# quadcopter.net
KiCad netlist of a schematic drawn in EAGLE
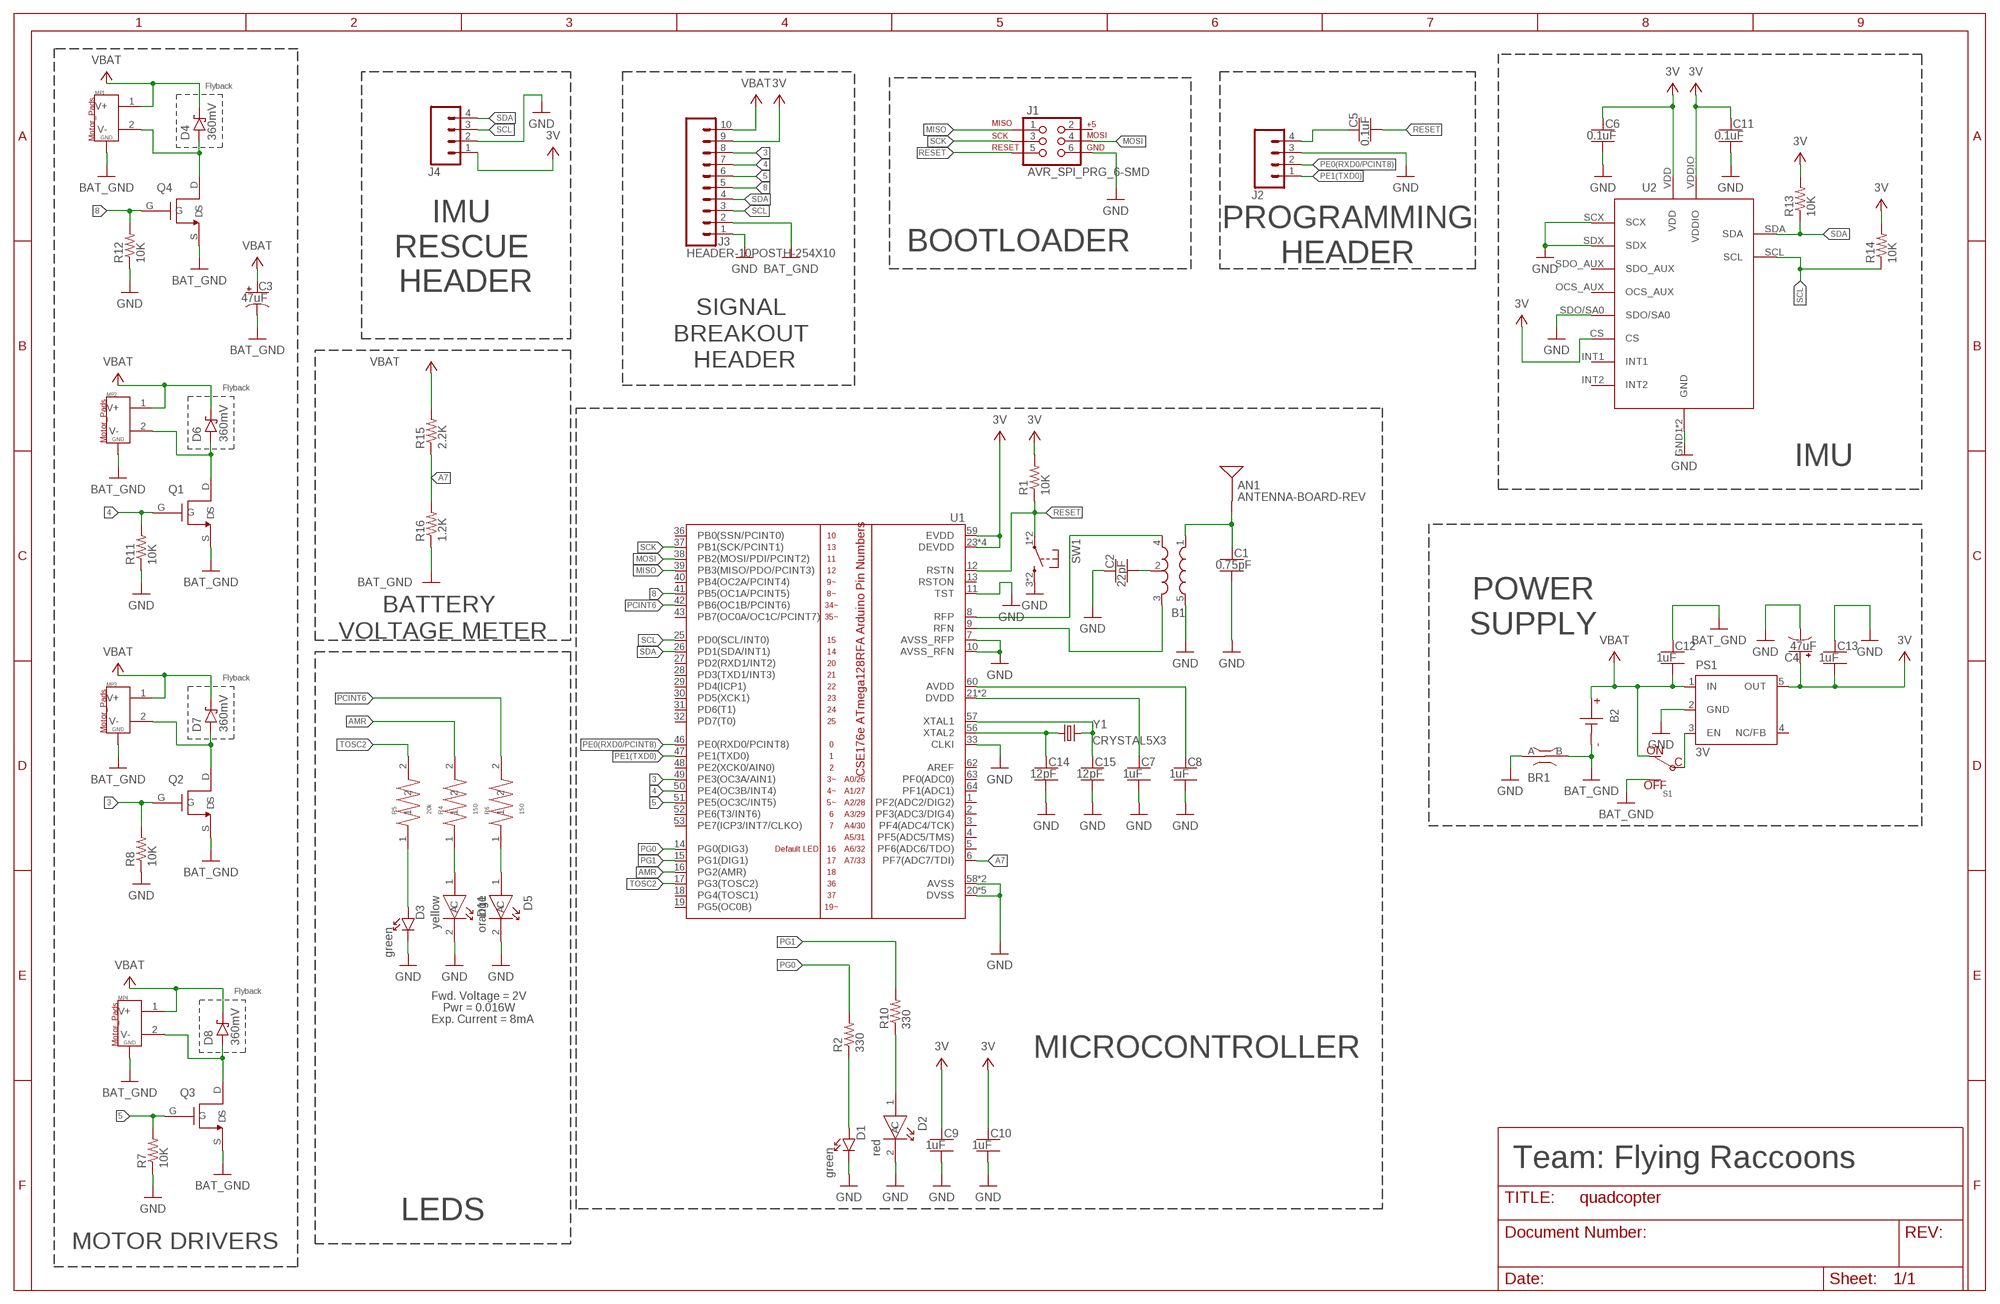
[diagram p0: schematic, sheet 1]

(export (version "E")
  (design (tool "Eeschema 10.0.6"))
  (components
    (comp (ref "AN1")
      (value "ANTENNA-BOARD-REV")
      (footprint "eagle-import:ANT_PCB_2.4GHZ_NRF8001_1.6MM_1OZ_REV")
      (fields (field (name "MFR") "NA") (field (name "CREATOR") "Swanson"))
      (libsource (lib "eagle-import") (part "ANTENNA-BOARD-REV"))
    )
    (comp (ref "B1")
      (value "BALUN0805")
      (footprint "eagle-import:BALUN")
      (fields
        (field (name "MFR") "Wurth Electronics Inc.")
        (field (name "MPN") "748421245")
        (field (name "CREATOR") "Swanson")
        (field (name "REVIEWER") "Swanson")
      )
      (libsource (lib "eagle-import") (part "BALUN0805"))
    )
    (comp (ref "B2")
      (value "BATTERY-SCREW-TERMINAL")
      (footprint "eagle-import:SCREW-TERMINAL-1X2-2.54MM")
      (fields (field (name "CREATOR") "Swanson"))
      (libsource (lib "eagle-import") (part "BATTERY-SCREW-TERMINAL"))
    )
    (comp (ref "BR1")
      (value "NET_BRIDGE-NET-BRIDGE")
      (footprint "eagle-import:BRIDGE")
      (fields (field (name "CREATOR") "Anish Kulkarni"))
      (libsource (lib "eagle-import") (part "NET_BRIDGE-NET-BRIDGE"))
    )
    (comp (ref "C1")
      (value "0.75pF")
      (footprint "eagle-import:CAPC2012X140_HS")
      (fields
        (field (name "MFR") "Murata Electronics")
        (field (name "MPN") "GQM2195C2AR75CB01D")
        (field (name "CREATOR") "Swanson")
        (field (name "REVIEWER") "Swanson")
      )
      (libsource (lib "eagle-import") (part "CAPACITOR-NP_SMD-2012-0805_CERAMIC-0.75PF"))
    )
    (comp (ref "C2")
      (value "22pF")
      (footprint "eagle-import:CAPC2012X140_HS")
      (fields
        (field (name "MFR") "Murata Electronics")
        (field (name "MPN") "GRM21A5C2E220JW01D")
        (field (name "CREATOR") "Swanson")
        (field (name "REVIEWER") "Swanson")
      )
      (libsource (lib "eagle-import") (part "CAPACITOR-NP_SMD-2012-0805_CERAMIC-22PF"))
    )
    (comp (ref "C3")
      (value "47uF")
      (footprint "eagle-import:CAPMP3216X180")
      (fields
        (field (name "MFR") "AVX Corporation")
        (field (name "MPN") "TAJA476K006SNJV")
        (field (name "CREATOR") "Swanson")
      )
      (libsource (lib "eagle-import") (part "CAPACITOR-POL_47UF-SMD-1206-TAJA"))
    )
    (comp (ref "C4")
      (value "47uF")
      (footprint "eagle-import:CAPMP3216X180")
      (fields
        (field (name "MFR") "AVX Corporation")
        (field (name "MPN") "TAJA476K006SNJV")
        (field (name "CREATOR") "Swanson")
      )
      (libsource (lib "eagle-import") (part "CAPACITOR-POL_47UF-SMD-1206-TAJA"))
    )
    (comp (ref "C5")
      (value "0.1uF")
      (footprint "eagle-import:CAPC2012X140_HS")
      (fields
        (field (name "MFR") "TDK Corporation")
        (field (name "MPN") "C2012X7R2A104K125AA")
        (field (name "CREATOR") "Swanson")
        (field (name "REVIEWER") "Swanson")
      )
      (libsource (lib "eagle-import") (part "CAPACITOR-NP_SMD-2012-0805_CERAMIC-0.1UF"))
    )
    (comp (ref "C6")
      (value "0.1uF")
      (footprint "eagle-import:CAPC2012X140_HS")
      (fields
        (field (name "MFR") "TDK Corporation")
        (field (name "MPN") "C2012X7R2A104K125AA")
        (field (name "CREATOR") "Swanson")
        (field (name "REVIEWER") "Swanson")
      )
      (libsource (lib "eagle-import") (part "CAPACITOR-NP_SMD-2012-0805_CERAMIC-0.1UF"))
    )
    (comp (ref "C7")
      (value "1uF")
      (footprint "eagle-import:CAPC2012X140_HS")
      (fields
        (field (name "MFR") "Taiyo Yuden")
        (field (name "MPN") "TMK212B7105KG-T")
        (field (name "CREATOR") "Swanson")
        (field (name "REVIEWER") "Swanson")
      )
      (libsource (lib "eagle-import") (part "CAPACITOR-NP_SMD-2012-0805_CERAMIC-1UF"))
    )
    (comp (ref "C8")
      (value "1uF")
      (footprint "eagle-import:CAPC2012X140_HS")
      (fields
        (field (name "MFR") "Taiyo Yuden")
        (field (name "MPN") "TMK212B7105KG-T")
        (field (name "CREATOR") "Swanson")
        (field (name "REVIEWER") "Swanson")
      )
      (libsource (lib "eagle-import") (part "CAPACITOR-NP_SMD-2012-0805_CERAMIC-1UF"))
    )
    (comp (ref "C9")
      (value "1uF")
      (footprint "eagle-import:CAPC2012X140_HS")
      (fields
        (field (name "MFR") "Taiyo Yuden")
        (field (name "MPN") "TMK212B7105KG-T")
        (field (name "CREATOR") "Swanson")
        (field (name "REVIEWER") "Swanson")
      )
      (libsource (lib "eagle-import") (part "CAPACITOR-NP_SMD-2012-0805_CERAMIC-1UF"))
    )
    (comp (ref "C10")
      (value "1uF")
      (footprint "eagle-import:CAPC2012X140_HS")
      (fields
        (field (name "MFR") "Taiyo Yuden")
        (field (name "MPN") "TMK212B7105KG-T")
        (field (name "CREATOR") "Swanson")
        (field (name "REVIEWER") "Swanson")
      )
      (libsource (lib "eagle-import") (part "CAPACITOR-NP_SMD-2012-0805_CERAMIC-1UF"))
    )
    (comp (ref "C11")
      (value "0.1uF")
      (footprint "eagle-import:CAPC2012X140_HS")
      (fields
        (field (name "MFR") "TDK Corporation")
        (field (name "MPN") "C2012X7R2A104K125AA")
        (field (name "CREATOR") "Swanson")
        (field (name "REVIEWER") "Swanson")
      )
      (libsource (lib "eagle-import") (part "CAPACITOR-NP_SMD-2012-0805_CERAMIC-0.1UF"))
    )
    (comp (ref "C12")
      (value "1uF")
      (footprint "eagle-import:CAPC2012X140_HS")
      (fields
        (field (name "MFR") "Taiyo Yuden")
        (field (name "MPN") "TMK212B7105KG-T")
        (field (name "CREATOR") "Swanson")
        (field (name "REVIEWER") "Swanson")
      )
      (libsource (lib "eagle-import") (part "CAPACITOR-NP_SMD-2012-0805_CERAMIC-1UF"))
    )
    (comp (ref "C13")
      (value "1uF")
      (footprint "eagle-import:CAPC2012X140_HS")
      (fields
        (field (name "MFR") "Taiyo Yuden")
        (field (name "MPN") "TMK212B7105KG-T")
        (field (name "CREATOR") "Swanson")
        (field (name "REVIEWER") "Swanson")
      )
      (libsource (lib "eagle-import") (part "CAPACITOR-NP_SMD-2012-0805_CERAMIC-1UF"))
    )
    (comp (ref "C14")
      (value "12pF")
      (footprint "eagle-import:CAPC2012X140_HS")
      (fields
        (field (name "MFR") "Murata Electronics")
        (field (name "MPN") "GRM21A5C2E120JW01D")
        (field (name "CREATOR") "Swanson")
        (field (name "REVIEWER") "Swanson")
      )
      (libsource (lib "eagle-import") (part "CAPACITOR-NP_SMD-2012-0805_CERAMIC-12PF"))
    )
    (comp (ref "C15")
      (value "12pF")
      (footprint "eagle-import:CAPC2012X140_HS")
      (fields
        (field (name "MFR") "Murata Electronics")
        (field (name "MPN") "GRM21A5C2E120JW01D")
        (field (name "CREATOR") "Swanson")
        (field (name "REVIEWER") "Swanson")
      )
      (libsource (lib "eagle-import") (part "CAPACITOR-NP_SMD-2012-0805_CERAMIC-12PF"))
    )
    (comp (ref "D1")
      (value "green")
      (footprint "eagle-import:LEDSC125X200X120-2_HS")
      (fields
        (field (name "MFR") "Lite-On Inc")
        (field (name "MPN") "LTST-C170GKT")
        (field (name "CREATOR") "Swanson")
        (field (name "REVIEWER") "Swanson")
      )
      (libsource (lib "eagle-import") (part "DIODE-LED_SMD-2012-0805-GREEN"))
    )
    (comp (ref "D2")
      (value "red")
      (footprint "eagle-import:LED-LTST-C170EKT")
      (fields (field (name "CREATOR") "Anish Kulkarni"))
      (libsource (lib "eagle-import") (part "LED-RED_D-C170EKT"))
    )
    (comp (ref "D3")
      (value "green")
      (footprint "eagle-import:LEDSC125X200X120-2_HS")
      (fields
        (field (name "MFR") "Lite-On Inc")
        (field (name "MPN") "LTST-C170GKT")
        (field (name "CREATOR") "Swanson")
        (field (name "REVIEWER") "Swanson")
      )
      (libsource (lib "eagle-import") (part "DIODE-LED_SMD-2012-0805-GREEN"))
    )
    (comp (ref "D4")
      (value "360mV")
      (footprint "eagle-import:SODFL3516X96")
      (fields
        (field (name "MFR") "Toshiba Semiconductor and Storage")
        (field (name "MPN") "CRS08(TE85L,Q,M)")
        (field (name "CREATOR") "Swanson")
        (field (name "REVIEWER") "Swanson")
      )
      (libsource (lib "eagle-import") (part "DIODE-SCHOTTKY_-SMD-SOD123"))
    )
    (comp (ref "D5")
      (value "orange")
      (footprint "eagle-import:LED-LTST-C170EKT")
      (fields (field (name "CREATOR") "Anish Kulkarni"))
      (libsource (lib "eagle-import") (part "LED-ORANGE_D-LOR976"))
    )
    (comp (ref "D6")
      (value "360mV")
      (footprint "eagle-import:SODFL3516X96")
      (fields
        (field (name "MFR") "Toshiba Semiconductor and Storage")
        (field (name "MPN") "CRS08(TE85L,Q,M)")
        (field (name "CREATOR") "Swanson")
        (field (name "REVIEWER") "Swanson")
      )
      (libsource (lib "eagle-import") (part "DIODE-SCHOTTKY_-SMD-SOD123"))
    )
    (comp (ref "D7")
      (value "360mV")
      (footprint "eagle-import:SODFL3516X96")
      (fields
        (field (name "MFR") "Toshiba Semiconductor and Storage")
        (field (name "MPN") "CRS08(TE85L,Q,M)")
        (field (name "CREATOR") "Swanson")
        (field (name "REVIEWER") "Swanson")
      )
      (libsource (lib "eagle-import") (part "DIODE-SCHOTTKY_-SMD-SOD123"))
    )
    (comp (ref "D8")
      (value "360mV")
      (footprint "eagle-import:SODFL3516X96")
      (fields
        (field (name "MFR") "Toshiba Semiconductor and Storage")
        (field (name "MPN") "CRS08(TE85L,Q,M)")
        (field (name "CREATOR") "Swanson")
        (field (name "REVIEWER") "Swanson")
      )
      (libsource (lib "eagle-import") (part "DIODE-SCHOTTKY_-SMD-SOD123"))
    )
    (comp (ref "D11")
      (value "yellow")
      (footprint "eagle-import:LED-LTST-C170EKT")
      (fields (field (name "CREATOR") "Anish Kulkarni"))
      (libsource (lib "eagle-import") (part "LED-YELLOW_D-LYR976"))
    )
    (comp (ref "J1")
      (value "AVR_SPI_PRG_6-SMD")
      (footprint "eagle-import:2X3-SMD")
      (fields
        (field (name "MFR") "Amphenol ICC (FCI)")
        (field (name "MPN") "95278-101A06LF")
        (field (name "CREATOR") "Swanson")
      )
      (libsource (lib "eagle-import") (part "AVR_SPI_PRG_6-SMD"))
    )
    (comp (ref "J2")
      (value "HEADER-4POS-0.1IN-FEMALE-SMD-BOTTOM-ENTRY")
      (footprint "eagle-import:HEADER-1X4-BOTTOM-ENTRY")
      (fields
        (field (name "MFR") "TE Connectivity AMP Connectors")
        (field (name "MPN") "1241152-4")
        (field (name "CREATOR") "Swanson")
      )
      (libsource (lib "eagle-import") (part "HEADER-4POS-0.1IN-FEMALE-SMD-BOTTOM-ENTRY"))
    )
    (comp (ref "J3")
      (value "HEADER-10POSTH-254X10")
      (footprint "eagle-import:HDRV10W63P254_10X1_2540X254H838_HS")
      (fields
        (field (name "MFR") "Amphenol FCI")
        (field (name "MPN") "68000-110HLF")
        (field (name "CREATOR") "Swanson")
        (field (name "REVIEWER") "Swanson")
      )
      (libsource (lib "eagle-import") (part "HEADER-10POSTH-254X10"))
    )
    (comp (ref "J4")
      (value "HEADER-4POS-0.1IN-FEMALE-SMD-BOTTOM-ENTRY")
      (footprint "eagle-import:HEADER-1X4-BOTTOM-ENTRY")
      (fields
        (field (name "MFR") "TE Connectivity AMP Connectors")
        (field (name "MPN") "1241152-4")
        (field (name "CREATOR") "Swanson")
      )
      (libsource (lib "eagle-import") (part "HEADER-4POS-0.1IN-FEMALE-SMD-BOTTOM-ENTRY"))
    )
    (comp (ref "MP1")
      (value "MOTOR_PADS_GND-MOLEX-SMD")
      (footprint "eagle-import:MOLEX-0532610271")
      (fields
        (field (name "MFR") "Molex")
        (field (name "MPN") "532610271")
        (field (name "CREATOR") "Swanson")
      )
      (libsource (lib "eagle-import") (part "MOTOR_PADS_GND-MOLEX-SMD"))
    )
    (comp (ref "MP2")
      (value "MOTOR_PADS_GND-MOLEX-SMD")
      (footprint "eagle-import:MOLEX-0532610271")
      (fields
        (field (name "MFR") "Molex")
        (field (name "MPN") "532610271")
        (field (name "CREATOR") "Swanson")
      )
      (libsource (lib "eagle-import") (part "MOTOR_PADS_GND-MOLEX-SMD"))
    )
    (comp (ref "MP3")
      (value "MOTOR_PADS_GND-MOLEX-SMD")
      (footprint "eagle-import:MOLEX-0532610271")
      (fields
        (field (name "MFR") "Molex")
        (field (name "MPN") "532610271")
        (field (name "CREATOR") "Swanson")
      )
      (libsource (lib "eagle-import") (part "MOTOR_PADS_GND-MOLEX-SMD"))
    )
    (comp (ref "MP4")
      (value "MOTOR_PADS_GND-MOLEX-SMD")
      (footprint "eagle-import:MOLEX-0532610271")
      (fields
        (field (name "MFR") "Molex")
        (field (name "MPN") "532610271")
        (field (name "CREATOR") "Swanson")
      )
      (libsource (lib "eagle-import") (part "MOTOR_PADS_GND-MOLEX-SMD"))
    )
    (comp (ref "PS1")
      (value "3V")
      (footprint "eagle-import:SOT23-DBV")
      (fields
        (field (name "MFR") "Texas Instruments")
        (field (name "MPN") "LP3985IM5X-3.0/NOPB")
        (field (name "CREATOR") "Swanson")
        (field (name "REVIEWER") "Swanson")
      )
      (libsource (lib "eagle-import") (part "TPS73633-DBVT3V"))
    )
    (comp (ref "Q1")
      (value "NMOSFET")
      (footprint "eagle-import:SOTFL95P237X112-3N")
      (fields (field (name "CREATOR") "GIRISH K"))
      (libsource (lib "eagle-import") (part "NMOSFET"))
    )
    (comp (ref "Q2")
      (value "NMOSFET")
      (footprint "eagle-import:SOTFL95P237X112-3N")
      (fields (field (name "CREATOR") "GIRISH K"))
      (libsource (lib "eagle-import") (part "NMOSFET"))
    )
    (comp (ref "Q3")
      (value "NMOSFET")
      (footprint "eagle-import:SOTFL95P237X112-3N")
      (fields (field (name "CREATOR") "GIRISH K"))
      (libsource (lib "eagle-import") (part "NMOSFET"))
    )
    (comp (ref "Q4")
      (value "NMOSFET")
      (footprint "eagle-import:SOTFL95P237X112-3N")
      (fields (field (name "CREATOR") "GIRISH K"))
      (libsource (lib "eagle-import") (part "NMOSFET"))
    )
    (comp (ref "R1")
      (value "10K")
      (footprint "eagle-import:RESC2012X60_HS")
      (fields
        (field (name "MFR") "Yageo")
        (field (name "MPN") "RC0805JR-0710KL")
        (field (name "CREATOR") "Swanson")
        (field (name "REVIEWER") "Swanson")
      )
      (libsource (lib "eagle-import") (part "RESISTOR_SMD-2012-0805-10K"))
    )
    (comp (ref "R2")
      (value "330")
      (footprint "eagle-import:RESC2012X60_HS")
      (fields
        (field (name "MFR") "Yageo")
        (field (name "MPN") "RC0805JR-07330RL")
        (field (name "CREATOR") "Swanson")
        (field (name "REVIEWER") "Swanson")
      )
      (libsource (lib "eagle-import") (part "RESISTOR_SMD-2012-0805-330"))
    )
    (comp (ref "R4")
      (value "150")
      (footprint "eagle-import:0805_RESISTOR")
      (fields (field (name "CREATOR") "GIRISH K"))
      (libsource (lib "eagle-import") (part "RESISTOR-150R-0805"))
    )
    (comp (ref "R5")
      (value "20k")
      (footprint "eagle-import:0805_RESISTOR")
      (fields (field (name "CREATOR") "GIRISH K"))
      (libsource (lib "eagle-import") (part "RESISTOR-20K-0805"))
    )
    (comp (ref "R6")
      (value "150")
      (footprint "eagle-import:0805_RESISTOR")
      (fields (field (name "CREATOR") "GIRISH K"))
      (libsource (lib "eagle-import") (part "RESISTOR-150R-0805"))
    )
    (comp (ref "R7")
      (value "10K")
      (footprint "eagle-import:RESC2012X60_HS")
      (fields
        (field (name "MFR") "Yageo")
        (field (name "MPN") "RC0805JR-0710KL")
        (field (name "CREATOR") "Swanson")
        (field (name "REVIEWER") "Swanson")
      )
      (libsource (lib "eagle-import") (part "RESISTOR_SMD-2012-0805-10K"))
    )
    (comp (ref "R8")
      (value "10K")
      (footprint "eagle-import:RESC2012X60_HS")
      (fields
        (field (name "MFR") "Yageo")
        (field (name "MPN") "RC0805JR-0710KL")
        (field (name "CREATOR") "Swanson")
        (field (name "REVIEWER") "Swanson")
      )
      (libsource (lib "eagle-import") (part "RESISTOR_SMD-2012-0805-10K"))
    )
    (comp (ref "R10")
      (value "330")
      (footprint "eagle-import:RESC2012X60_HS")
      (fields
        (field (name "MFR") "Yageo")
        (field (name "MPN") "RC0805JR-07330RL")
        (field (name "CREATOR") "Swanson")
        (field (name "REVIEWER") "Swanson")
      )
      (libsource (lib "eagle-import") (part "RESISTOR_SMD-2012-0805-330"))
    )
    (comp (ref "R11")
      (value "10K")
      (footprint "eagle-import:RESC2012X60_HS")
      (fields
        (field (name "MFR") "Yageo")
        (field (name "MPN") "RC0805JR-0710KL")
        (field (name "CREATOR") "Swanson")
        (field (name "REVIEWER") "Swanson")
      )
      (libsource (lib "eagle-import") (part "RESISTOR_SMD-2012-0805-10K"))
    )
    (comp (ref "R12")
      (value "10K")
      (footprint "eagle-import:RESC2012X60_HS")
      (fields
        (field (name "MFR") "Yageo")
        (field (name "MPN") "RC0805JR-0710KL")
        (field (name "CREATOR") "Swanson")
        (field (name "REVIEWER") "Swanson")
      )
      (libsource (lib "eagle-import") (part "RESISTOR_SMD-2012-0805-10K"))
    )
    (comp (ref "R13")
      (value "10K")
      (footprint "eagle-import:RESC2012X60_HS")
      (fields
        (field (name "MFR") "Yageo")
        (field (name "MPN") "RC0805JR-0710KL")
        (field (name "CREATOR") "Swanson")
        (field (name "REVIEWER") "Swanson")
      )
      (libsource (lib "eagle-import") (part "RESISTOR_SMD-2012-0805-10K"))
    )
    (comp (ref "R14")
      (value "10K")
      (footprint "eagle-import:RESC2012X60_HS")
      (fields
        (field (name "MFR") "Yageo")
        (field (name "MPN") "RC0805JR-0710KL")
        (field (name "CREATOR") "Swanson")
        (field (name "REVIEWER") "Swanson")
      )
      (libsource (lib "eagle-import") (part "RESISTOR_SMD-2012-0805-10K"))
    )
    (comp (ref "R15")
      (value "2.2K")
      (footprint "eagle-import:RESC2012X60_HS")
      (fields (field (name "CREATOR") "SWANSON"))
      (libsource (lib "eagle-import") (part "RESISTOR_SMD-2012-0805-2.2K"))
    )
    (comp (ref "R16")
      (value "1.2K")
      (footprint "eagle-import:RESC2012X60_HS")
      (fields
        (field (name "MFR") "Yageo")
        (field (name "MPN") "RC0805FR-071K2L")
        (field (name "CREATOR") "Swanson")
      )
      (libsource (lib "eagle-import") (part "RESISTOR_SMD-2012-0805-1.2K"))
    )
    (comp (ref "S1")
      (value "POWER-SWITCH-MFS201N-9-Z-SMD-EDGE")
      (footprint "eagle-import:JS102011SAQN")
      (fields
        (field (name "MFR") "C&K")
        (field (name "MPN") "JS102011SAQN")
        (field (name "CREATOR") "Swanson")
      )
      (libsource (lib "eagle-import") (part "POWER-SWITCH-MFS201N-9-Z-SMD-EDGE"))
    )
    (comp (ref "SW1")
      (value "PUSHBUTTON_-4.5X4.5")
      (footprint "eagle-import:4.5MM_TACTILE_SWITCH_TL3305AF160QG")
      (fields
        (field (name "MFR") "E-Switch")
        (field (name "MPN") "TL3305AF160QG")
        (field (name "CREATOR") "Swanson")
      )
      (libsource (lib "eagle-import") (part "PUSHBUTTON_-4.5X4.5"))
    )
    (comp (ref "U1")
      (value "ATMEGA128RFA1")
      (footprint "eagle-import:QFN-64")
      (fields
        (field (name "MFR") "Microchip Technology")
        (field (name "MPN") "ATMEGA128RFA1-ZU")
        (field (name "CREATOR") "Swanson")
        (field (name "REVIEWER") "Swanson")
      )
      (libsource (lib "eagle-import") (part "ATMEGA128RFA1"))
    )
    (comp (ref "U2")
      (value "IMU_LSM6DS0XTR-IMU-LSM6DS0XTR")
      (footprint "eagle-import:IMU_LSM6DS0XTR")
      (fields (field (name "CREATOR") "GIRISH K"))
      (libsource (lib "eagle-import") (part "IMU_LSM6DS0XTR-IMU-LSM6DS0XTR"))
    )
    (comp (ref "Y1")
      (value "CRYSTAL5X3")
      (footprint "eagle-import:CRYSTAL-SMD-5X3")
      (fields
        (field (name "MFR") "Abracon LLC")
        (field (name "MPN") "ABM3B-16.000MHZ-B2-T")
        (field (name "CREATOR") "Swanson")
        (field (name "REVIEWER") "Swanson")
      )
      (libsource (lib "eagle-import") (part "CRYSTAL5X3"))
    )
  )
  (nets
    (net (code "1") (name "3") (class "Default")
      (node (ref "J3") (pin "8") (pinfunction "8_8") (pintype "passive"))
      (node (ref "Q2") (pin "G") (pinfunction "G_G") (pintype "bidirectional"))
      (node (ref "R8") (pin "2") (pinfunction "2_2") (pintype "passive"))
      (node (ref "U1") (pin "49") (pinfunction "PE3(OC3A/AIN1)_49") (pintype "bidirectional"))
    )
    (net (code "2") (name "3V") (class "Default")
      (node (ref "C10") (pin "1") (pinfunction "1_1") (pintype "passive"))
      (node (ref "C11") (pin "1") (pinfunction "1_1") (pintype "passive"))
      (node (ref "C13") (pin "2") (pinfunction "2_2") (pintype "passive"))
      (node (ref "C4") (pin "1") (pinfunction "+_1") (pintype "passive"))
      (node (ref "C6") (pin "1") (pinfunction "1_1") (pintype "passive"))
      (node (ref "C9") (pin "1") (pinfunction "1_1") (pintype "passive"))
      (node (ref "J3") (pin "9") (pinfunction "9_9") (pintype "passive"))
      (node (ref "J4") (pin "1") (pinfunction "1_1") (pintype "bidirectional"))
      (node (ref "PS1") (pin "5") (pinfunction "OUT_5") (pintype "passive"))
      (node (ref "R1") (pin "2") (pinfunction "2_2") (pintype "passive"))
      (node (ref "R13") (pin "2") (pinfunction "2_2") (pintype "passive"))
      (node (ref "R14") (pin "2") (pinfunction "2_2") (pintype "passive"))
      (node (ref "U1") (pin "23") (pinfunction "DEVDD_23") (pintype "bidirectional"))
      (node (ref "U1") (pin "34") (pinfunction "DEVDD_34") (pintype "bidirectional"))
      (node (ref "U1") (pin "44") (pinfunction "DEVDD_44") (pintype "bidirectional"))
      (node (ref "U1") (pin "54") (pinfunction "DEVDD_54") (pintype "bidirectional"))
      (node (ref "U1") (pin "59") (pinfunction "EVDD_59") (pintype "bidirectional"))
      (node (ref "U2") (pin "CS") (pinfunction "CS_CS") (pintype "bidirectional"))
      (node (ref "U2") (pin "VDD") (pinfunction "VDD_VDD") (pintype "bidirectional"))
      (node (ref "U2") (pin "VDDIO") (pinfunction "VDDIO_VDDIO") (pintype "bidirectional"))
    )
    (net (code "3") (name "4") (class "Default")
      (node (ref "J3") (pin "7") (pinfunction "7_7") (pintype "passive"))
      (node (ref "Q1") (pin "G") (pinfunction "G_G") (pintype "bidirectional"))
      (node (ref "R11") (pin "2") (pinfunction "2_2") (pintype "passive"))
      (node (ref "U1") (pin "50") (pinfunction "PE4(OC3B/INT4)_50") (pintype "bidirectional"))
    )
    (net (code "4") (name "5") (class "Default")
      (node (ref "J3") (pin "6") (pinfunction "6_6") (pintype "passive"))
      (node (ref "Q3") (pin "G") (pinfunction "G_G") (pintype "bidirectional"))
      (node (ref "R7") (pin "2") (pinfunction "2_2") (pintype "passive"))
      (node (ref "U1") (pin "51") (pinfunction "PE5(OC3C/INT5)_51") (pintype "bidirectional"))
    )
    (net (code "5") (name "8") (class "Default")
      (node (ref "J3") (pin "5") (pinfunction "5_5") (pintype "passive"))
      (node (ref "Q4") (pin "G") (pinfunction "G_G") (pintype "bidirectional"))
      (node (ref "R12") (pin "2") (pinfunction "2_2") (pintype "passive"))
      (node (ref "U1") (pin "41") (pinfunction "PB5(OC1A/PCINT5)_41") (pintype "bidirectional"))
    )
    (net (code "6") (name "A7") (class "Default")
      (node (ref "R15") (pin "1") (pinfunction "1_1") (pintype "passive"))
      (node (ref "R16") (pin "2") (pinfunction "2_2") (pintype "passive"))
      (node (ref "U1") (pin "6") (pinfunction "PF7(ADC7/TDI)_6") (pintype "bidirectional"))
    )
    (net (code "7") (name "AMR") (class "Default")
      (node (ref "R4") (pin "2") (pinfunction "2_2") (pintype "bidirectional"))
      (node (ref "U1") (pin "16") (pinfunction "PG2(AMR)_16") (pintype "bidirectional"))
    )
    (net (code "8") (name "BAT_GND") (class "Default")
      (node (ref "B2") (pin "1") (pinfunction "N_1") (pintype "bidirectional"))
      (node (ref "BR1") (pin "B") (pinfunction "B_B") (pintype "bidirectional"))
      (node (ref "C12") (pin "1") (pinfunction "1_1") (pintype "passive"))
      (node (ref "C3") (pin "2") (pinfunction "-_2") (pintype "passive"))
      (node (ref "J3") (pin "2") (pinfunction "2_2") (pintype "passive"))
      (node (ref "MP1") (pin "G1") (pinfunction "GND_G1") (pintype "bidirectional"))
      (node (ref "MP1") (pin "G2") (pinfunction "GND_G2") (pintype "bidirectional"))
      (node (ref "MP2") (pin "G1") (pinfunction "GND_G1") (pintype "bidirectional"))
      (node (ref "MP2") (pin "G2") (pinfunction "GND_G2") (pintype "bidirectional"))
      (node (ref "MP3") (pin "G1") (pinfunction "GND_G1") (pintype "bidirectional"))
      (node (ref "MP3") (pin "G2") (pinfunction "GND_G2") (pintype "bidirectional"))
      (node (ref "MP4") (pin "G1") (pinfunction "GND_G1") (pintype "bidirectional"))
      (node (ref "MP4") (pin "G2") (pinfunction "GND_G2") (pintype "bidirectional"))
      (node (ref "Q1") (pin "S") (pinfunction "S_S") (pintype "bidirectional"))
      (node (ref "Q2") (pin "S") (pinfunction "S_S") (pintype "bidirectional"))
      (node (ref "Q3") (pin "S") (pinfunction "S_S") (pintype "bidirectional"))
      (node (ref "Q4") (pin "S") (pinfunction "S_S") (pintype "bidirectional"))
      (node (ref "R16") (pin "1") (pinfunction "1_1") (pintype "passive"))
      (node (ref "S1") (pin "A") (pinfunction "OFF_A") (pintype "bidirectional"))
    )
    (net (code "9") (name "GND") (class "Default")
      (node (ref "B1") (pin "5") (pinfunction "GND_5") (pintype "bidirectional"))
      (node (ref "BR1") (pin "A") (pinfunction "A_A") (pintype "bidirectional"))
      (node (ref "C1") (pin "2") (pinfunction "2_2") (pintype "passive"))
      (node (ref "C10") (pin "2") (pinfunction "2_2") (pintype "passive"))
      (node (ref "C11") (pin "2") (pinfunction "2_2") (pintype "passive"))
      (node (ref "C13") (pin "1") (pinfunction "1_1") (pintype "passive"))
      (node (ref "C14") (pin "2") (pinfunction "2_2") (pintype "passive"))
      (node (ref "C15") (pin "2") (pinfunction "2_2") (pintype "passive"))
      (node (ref "C2") (pin "1") (pinfunction "1_1") (pintype "passive"))
      (node (ref "C4") (pin "2") (pinfunction "-_2") (pintype "passive"))
      (node (ref "C6") (pin "2") (pinfunction "2_2") (pintype "passive"))
      (node (ref "C7") (pin "2") (pinfunction "2_2") (pintype "passive"))
      (node (ref "C8") (pin "2") (pinfunction "2_2") (pintype "passive"))
      (node (ref "C9") (pin "2") (pinfunction "2_2") (pintype "passive"))
      (node (ref "D1") (pin "C") (pinfunction "C_C") (pintype "passive"))
      (node (ref "D11") (pin "2") (pinfunction "C_2") (pintype "bidirectional"))
      (node (ref "D2") (pin "2") (pinfunction "C_2") (pintype "bidirectional"))
      (node (ref "D3") (pin "C") (pinfunction "C_C") (pintype "passive"))
      (node (ref "D5") (pin "2") (pinfunction "C_2") (pintype "bidirectional"))
      (node (ref "J1") (pin "6") (pinfunction "6_6") (pintype "passive"))
      (node (ref "J2") (pin "3") (pinfunction "3_3") (pintype "bidirectional"))
      (node (ref "J3") (pin "1") (pinfunction "1_1") (pintype "passive"))
      (node (ref "J4") (pin "2") (pinfunction "2_2") (pintype "bidirectional"))
      (node (ref "PS1") (pin "2") (pinfunction "GND_2") (pintype "input"))
      (node (ref "R11") (pin "1") (pinfunction "1_1") (pintype "passive"))
      (node (ref "R12") (pin "1") (pinfunction "1_1") (pintype "passive"))
      (node (ref "R7") (pin "1") (pinfunction "1_1") (pintype "passive"))
      (node (ref "R8") (pin "1") (pinfunction "1_1") (pintype "passive"))
      (node (ref "SW1") (pin "3") (pinfunction "2_3") (pintype "passive"))
      (node (ref "SW1") (pin "4") (pinfunction "2_4") (pintype "passive"))
      (node (ref "U1") (pin "10") (pinfunction "AVSS_RFN_10") (pintype "bidirectional"))
      (node (ref "U1") (pin "11") (pinfunction "TST_11") (pintype "bidirectional"))
      (node (ref "U1") (pin "20") (pinfunction "DVSS_20") (pintype "bidirectional"))
      (node (ref "U1") (pin "24") (pinfunction "DVSS_24") (pintype "bidirectional"))
      (node (ref "U1") (pin "33") (pinfunction "CLKI_33") (pintype "bidirectional"))
      (node (ref "U1") (pin "35") (pinfunction "DVSS_35") (pintype "bidirectional"))
      (node (ref "U1") (pin "45") (pinfunction "DVSS_45") (pintype "bidirectional"))
      (node (ref "U1") (pin "55") (pinfunction "DVSS_55") (pintype "bidirectional"))
      (node (ref "U1") (pin "58") (pinfunction "AVSS_58") (pintype "bidirectional"))
      (node (ref "U1") (pin "61") (pinfunction "AVSS_61") (pintype "bidirectional"))
      (node (ref "U1") (pin "7") (pinfunction "AVSS_RFP_7") (pintype "bidirectional"))
      (node (ref "U2") (pin "GND1") (pinfunction "GND_GND1") (pintype "bidirectional"))
      (node (ref "U2") (pin "GND2") (pinfunction "GND_GND2") (pintype "bidirectional"))
      (node (ref "U2") (pin "SCX") (pinfunction "SCX_SCX") (pintype "bidirectional"))
      (node (ref "U2") (pin "SDO/SA0") (pinfunction "SDO/SA0_SDO/SA0") (pintype "bidirectional"))
      (node (ref "U2") (pin "SDX") (pinfunction "SDX_SDX") (pintype "bidirectional"))
    )
    (net (code "10") (name "MISO") (class "Default")
      (node (ref "J1") (pin "1") (pinfunction "1_1") (pintype "passive"))
      (node (ref "U1") (pin "39") (pinfunction "PB3(MISO/PDO/PCINT3)_39") (pintype "bidirectional"))
    )
    (net (code "11") (name "MOSI") (class "Default")
      (node (ref "J1") (pin "4") (pinfunction "4_4") (pintype "passive"))
      (node (ref "U1") (pin "38") (pinfunction "PB2(MOSI/PDI/PCINT2)_38") (pintype "bidirectional"))
    )
    (net (code "12") (name "Net-(AN1-SIGNAL)") (class "Default")
      (node (ref "AN1") (pin "FEED") (pinfunction "SIGNAL_FEED") (pintype "bidirectional"))
      (node (ref "B1") (pin "1") (pinfunction "IN_1") (pintype "bidirectional"))
      (node (ref "C1") (pin "1") (pinfunction "1_1") (pintype "passive"))
    )
    (net (code "13") (name "Net-(B1-GND-Pad2)") (class "Default")
      (node (ref "B1") (pin "2") (pinfunction "GND_2") (pintype "bidirectional"))
      (node (ref "C2") (pin "2") (pinfunction "2_2") (pintype "passive"))
    )
    (net (code "14") (name "Net-(B1-OUT1)") (class "Default")
      (node (ref "B1") (pin "4") (pinfunction "OUT1_4") (pintype "bidirectional"))
      (node (ref "U1") (pin "8") (pinfunction "RFP_8") (pintype "bidirectional"))
    )
    (net (code "15") (name "Net-(B1-OUT2)") (class "Default")
      (node (ref "B1") (pin "3") (pinfunction "OUT2_3") (pintype "bidirectional"))
      (node (ref "U1") (pin "9") (pinfunction "RFN_9") (pintype "bidirectional"))
    )
    (net (code "16") (name "Net-(C5-Pad1)") (class "Default")
      (node (ref "C5") (pin "1") (pinfunction "1_1") (pintype "passive"))
      (node (ref "J2") (pin "4") (pinfunction "4_4") (pintype "bidirectional"))
    )
    (net (code "17") (name "Net-(C7-Pad1)") (class "Default")
      (node (ref "C7") (pin "1") (pinfunction "1_1") (pintype "passive"))
      (node (ref "U1") (pin "21") (pinfunction "DVDD_21") (pintype "bidirectional"))
      (node (ref "U1") (pin "22") (pinfunction "DVDD_22") (pintype "bidirectional"))
    )
    (net (code "18") (name "Net-(D1-PadA)") (class "Default")
      (node (ref "D1") (pin "A") (pinfunction "A_A") (pintype "passive"))
      (node (ref "R2") (pin "1") (pinfunction "1_1") (pintype "passive"))
    )
    (net (code "19") (name "Net-(D2-A)") (class "Default")
      (node (ref "D2") (pin "1") (pinfunction "A_1") (pintype "bidirectional"))
      (node (ref "R10") (pin "1") (pinfunction "1_1") (pintype "passive"))
    )
    (net (code "20") (name "Net-(D3-PadA)") (class "Default")
      (node (ref "D3") (pin "A") (pinfunction "A_A") (pintype "passive"))
      (node (ref "R5") (pin "1") (pinfunction "1_1") (pintype "bidirectional"))
    )
    (net (code "21") (name "Net-(D4-A)") (class "Default")
      (node (ref "D4") (pin "2") (pinfunction "A_2") (pintype "passive"))
      (node (ref "MP1") (pin "2") (pinfunction "V-_2") (pintype "bidirectional"))
      (node (ref "Q4") (pin "D") (pinfunction "D_D") (pintype "bidirectional"))
    )
    (net (code "22") (name "Net-(D5-A)") (class "Default")
      (node (ref "D5") (pin "1") (pinfunction "A_1") (pintype "bidirectional"))
      (node (ref "R6") (pin "1") (pinfunction "1_1") (pintype "bidirectional"))
    )
    (net (code "23") (name "Net-(D6-A)") (class "Default")
      (node (ref "D6") (pin "2") (pinfunction "A_2") (pintype "passive"))
      (node (ref "MP2") (pin "2") (pinfunction "V-_2") (pintype "bidirectional"))
      (node (ref "Q1") (pin "D") (pinfunction "D_D") (pintype "bidirectional"))
    )
    (net (code "24") (name "Net-(D7-A)") (class "Default")
      (node (ref "D7") (pin "2") (pinfunction "A_2") (pintype "passive"))
      (node (ref "MP3") (pin "2") (pinfunction "V-_2") (pintype "bidirectional"))
      (node (ref "Q2") (pin "D") (pinfunction "D_D") (pintype "bidirectional"))
    )
    (net (code "25") (name "Net-(D8-A)") (class "Default")
      (node (ref "D8") (pin "2") (pinfunction "A_2") (pintype "passive"))
      (node (ref "MP4") (pin "2") (pinfunction "V-_2") (pintype "bidirectional"))
      (node (ref "Q3") (pin "D") (pinfunction "D_D") (pintype "bidirectional"))
    )
    (net (code "26") (name "Net-(D11-A)") (class "Default")
      (node (ref "D11") (pin "1") (pinfunction "A_1") (pintype "bidirectional"))
      (node (ref "R4") (pin "1") (pinfunction "1_1") (pintype "bidirectional"))
    )
    (net (code "27") (name "Net-(PS1-EN)") (class "Default")
      (node (ref "PS1") (pin "3") (pinfunction "EN_3") (pintype "input"))
      (node (ref "S1") (pin "C") (pinfunction "C_C") (pintype "bidirectional"))
    )
    (net (code "28") (name "Net-(U1-AVDD)") (class "Default")
      (node (ref "C8") (pin "1") (pinfunction "1_1") (pintype "passive"))
      (node (ref "U1") (pin "60") (pinfunction "AVDD_60") (pintype "bidirectional"))
    )
    (net (code "29") (name "Net-(U1-XTAL1)") (class "Default")
      (node (ref "C15") (pin "1") (pinfunction "1_1") (pintype "passive"))
      (node (ref "U1") (pin "57") (pinfunction "XTAL1_57") (pintype "bidirectional"))
      (node (ref "Y1") (pin "3") (pinfunction "2_3") (pintype "passive"))
    )
    (net (code "30") (name "Net-(U1-XTAL2)") (class "Default")
      (node (ref "C14") (pin "1") (pinfunction "1_1") (pintype "passive"))
      (node (ref "U1") (pin "56") (pinfunction "XTAL2_56") (pintype "bidirectional"))
      (node (ref "Y1") (pin "1") (pinfunction "1_1") (pintype "passive"))
    )
    (net (code "31") (name "PCINT6") (class "Default")
      (node (ref "R6") (pin "2") (pinfunction "2_2") (pintype "bidirectional"))
      (node (ref "U1") (pin "42") (pinfunction "PB6(OC1B/PCINT6)_42") (pintype "bidirectional"))
    )
    (net (code "32") (name "PE0(RXD0{slash}PCINT8)") (class "Default")
      (node (ref "J2") (pin "2") (pinfunction "2_2") (pintype "bidirectional"))
      (node (ref "U1") (pin "46") (pinfunction "PE0(RXD0/PCINT8)_46") (pintype "bidirectional"))
    )
    (net (code "33") (name "PE1(TXD0)") (class "Default")
      (node (ref "J2") (pin "1") (pinfunction "1_1") (pintype "bidirectional"))
      (node (ref "U1") (pin "47") (pinfunction "PE1(TXD0)_47") (pintype "bidirectional"))
    )
    (net (code "34") (name "PG0") (class "Default")
      (node (ref "R2") (pin "2") (pinfunction "2_2") (pintype "passive"))
      (node (ref "U1") (pin "14") (pinfunction "PG0(DIG3)_14") (pintype "bidirectional"))
    )
    (net (code "35") (name "PG1") (class "Default")
      (node (ref "R10") (pin "2") (pinfunction "2_2") (pintype "passive"))
      (node (ref "U1") (pin "15") (pinfunction "PG1(DIG1)_15") (pintype "bidirectional"))
    )
    (net (code "36") (name "RESET") (class "Default")
      (node (ref "C5") (pin "2") (pinfunction "2_2") (pintype "passive"))
      (node (ref "J1") (pin "5") (pinfunction "5_5") (pintype "passive"))
      (node (ref "R1") (pin "1") (pinfunction "1_1") (pintype "passive"))
      (node (ref "SW1") (pin "1") (pinfunction "1_1") (pintype "passive"))
      (node (ref "SW1") (pin "2") (pinfunction "1_2") (pintype "passive"))
      (node (ref "U1") (pin "12") (pinfunction "RSTN_12") (pintype "bidirectional"))
    )
    (net (code "37") (name "SCK") (class "Default")
      (node (ref "J1") (pin "3") (pinfunction "3_3") (pintype "passive"))
      (node (ref "U1") (pin "37") (pinfunction "PB1(SCK/PCINT1)_37") (pintype "bidirectional"))
    )
    (net (code "38") (name "SCL") (class "Default")
      (node (ref "J3") (pin "3") (pinfunction "3_3") (pintype "passive"))
      (node (ref "J4") (pin "3") (pinfunction "3_3") (pintype "bidirectional"))
      (node (ref "R14") (pin "1") (pinfunction "1_1") (pintype "passive"))
      (node (ref "U1") (pin "25") (pinfunction "PD0(SCL/INT0)_25") (pintype "bidirectional"))
      (node (ref "U2") (pin "SCL") (pinfunction "SCL_SCL") (pintype "bidirectional"))
    )
    (net (code "39") (name "SDA") (class "Default")
      (node (ref "J3") (pin "4") (pinfunction "4_4") (pintype "passive"))
      (node (ref "J4") (pin "4") (pinfunction "4_4") (pintype "bidirectional"))
      (node (ref "R13") (pin "1") (pinfunction "1_1") (pintype "passive"))
      (node (ref "U1") (pin "26") (pinfunction "PD1(SDA/INT1)_26") (pintype "bidirectional"))
      (node (ref "U2") (pin "SDA") (pinfunction "SDA_SDA") (pintype "bidirectional"))
    )
    (net (code "40") (name "TOSC2") (class "Default")
      (node (ref "R5") (pin "2") (pinfunction "2_2") (pintype "bidirectional"))
      (node (ref "U1") (pin "17") (pinfunction "PG3(TOSC2)_17") (pintype "bidirectional"))
    )
    (net (code "41") (name "VBAT") (class "Default")
      (node (ref "B2") (pin "2") (pinfunction "P_2") (pintype "bidirectional"))
      (node (ref "C12") (pin "2") (pinfunction "2_2") (pintype "passive"))
      (node (ref "C3") (pin "1") (pinfunction "+_1") (pintype "passive"))
      (node (ref "D4") (pin "1") (pinfunction "C_1") (pintype "passive"))
      (node (ref "D6") (pin "1") (pinfunction "C_1") (pintype "passive"))
      (node (ref "D7") (pin "1") (pinfunction "C_1") (pintype "passive"))
      (node (ref "D8") (pin "1") (pinfunction "C_1") (pintype "passive"))
      (node (ref "J3") (pin "10") (pinfunction "10_10") (pintype "passive"))
      (node (ref "MP1") (pin "1") (pinfunction "V+_1") (pintype "bidirectional"))
      (node (ref "MP2") (pin "1") (pinfunction "V+_1") (pintype "bidirectional"))
      (node (ref "MP3") (pin "1") (pinfunction "V+_1") (pintype "bidirectional"))
      (node (ref "MP4") (pin "1") (pinfunction "V+_1") (pintype "bidirectional"))
      (node (ref "PS1") (pin "1") (pinfunction "IN_1") (pintype "input"))
      (node (ref "R15") (pin "2") (pinfunction "2_2") (pintype "passive"))
      (node (ref "S1") (pin "B") (pinfunction "ON_B") (pintype "bidirectional"))
    )
    (net (code "42") (name "unconnected-(J1-Pad2)") (class "Default")
      (node (ref "J1") (pin "2") (pinfunction "2_2") (pintype "passive"))
    )
    (net (code "43") (name "unconnected-(PS1-NC{slash}FB-Pad4)") (class "Default")
      (node (ref "PS1") (pin "4") (pinfunction "NC/FB_4") (pintype "passive"))
    )
    (net (code "44") (name "unconnected-(U1-AREF-Pad62)") (class "Default")
      (node (ref "U1") (pin "62") (pinfunction "AREF_62") (pintype "bidirectional"))
    )
    (net (code "45") (name "unconnected-(U1-PB0(SSN{slash}PCINT0)-Pad36)") (class "Default")
      (node (ref "U1") (pin "36") (pinfunction "PB0(SSN/PCINT0)_36") (pintype "bidirectional"))
    )
    (net (code "46") (name "unconnected-(U1-PB4(OC2A{slash}PCINT4)-Pad40)") (class "Default")
      (node (ref "U1") (pin "40") (pinfunction "PB4(OC2A/PCINT4)_40") (pintype "bidirectional"))
    )
    (net (code "47") (name "unconnected-(U1-PB7(OC0A{slash}OC1C{slash}PCINT7)-Pad43)") (class "Default")
      (node (ref "U1") (pin "43") (pinfunction "PB7(OC0A/OC1C/PCINT7)_43") (pintype "bidirectional"))
    )
    (net (code "48") (name "unconnected-(U1-PD2(RXD1{slash}INT2)-Pad27)") (class "Default")
      (node (ref "U1") (pin "27") (pinfunction "PD2(RXD1/INT2)_27") (pintype "bidirectional"))
    )
    (net (code "49") (name "unconnected-(U1-PD3(TXD1{slash}INT3)-Pad28)") (class "Default")
      (node (ref "U1") (pin "28") (pinfunction "PD3(TXD1/INT3)_28") (pintype "bidirectional"))
    )
    (net (code "50") (name "unconnected-(U1-PD4(ICP1)-Pad29)") (class "Default")
      (node (ref "U1") (pin "29") (pinfunction "PD4(ICP1)_29") (pintype "bidirectional"))
    )
    (net (code "51") (name "unconnected-(U1-PD5(XCK1)-Pad30)") (class "Default")
      (node (ref "U1") (pin "30") (pinfunction "PD5(XCK1)_30") (pintype "bidirectional"))
    )
    (net (code "52") (name "unconnected-(U1-PD6(T1)-Pad31)") (class "Default")
      (node (ref "U1") (pin "31") (pinfunction "PD6(T1)_31") (pintype "bidirectional"))
    )
    (net (code "53") (name "unconnected-(U1-PD7(T0)-Pad32)") (class "Default")
      (node (ref "U1") (pin "32") (pinfunction "PD7(T0)_32") (pintype "bidirectional"))
    )
    (net (code "54") (name "unconnected-(U1-PE2(XCK0{slash}AIN0)-Pad48)") (class "Default")
      (node (ref "U1") (pin "48") (pinfunction "PE2(XCK0/AIN0)_48") (pintype "bidirectional"))
    )
    (net (code "55") (name "unconnected-(U1-PE6(T3{slash}INT6)-Pad52)") (class "Default")
      (node (ref "U1") (pin "52") (pinfunction "PE6(T3/INT6)_52") (pintype "bidirectional"))
    )
    (net (code "56") (name "unconnected-(U1-PE7(ICP3{slash}INT7{slash}CLKO)-Pad53)") (class "Default")
      (node (ref "U1") (pin "53") (pinfunction "PE7(ICP3/INT7/CLKO)_53") (pintype "bidirectional"))
    )
    (net (code "57") (name "unconnected-(U1-PF0(ADC0)-Pad63)") (class "Default")
      (node (ref "U1") (pin "63") (pinfunction "PF0(ADC0)_63") (pintype "bidirectional"))
    )
    (net (code "58") (name "unconnected-(U1-PF1(ADC1)-Pad64)") (class "Default")
      (node (ref "U1") (pin "64") (pinfunction "PF1(ADC1)_64") (pintype "bidirectional"))
    )
    (net (code "59") (name "unconnected-(U1-PF2(ADC2{slash}DIG2)-Pad1)") (class "Default")
      (node (ref "U1") (pin "1") (pinfunction "PF2(ADC2/DIG2)_1") (pintype "bidirectional"))
    )
    (net (code "60") (name "unconnected-(U1-PF3(ADC3{slash}DIG4)-Pad2)") (class "Default")
      (node (ref "U1") (pin "2") (pinfunction "PF3(ADC3/DIG4)_2") (pintype "bidirectional"))
    )
    (net (code "61") (name "unconnected-(U1-PF4(ADC4{slash}TCK)-Pad3)") (class "Default")
      (node (ref "U1") (pin "3") (pinfunction "PF4(ADC4/TCK)_3") (pintype "bidirectional"))
    )
    (net (code "62") (name "unconnected-(U1-PF5(ADC5{slash}TMS)-Pad4)") (class "Default")
      (node (ref "U1") (pin "4") (pinfunction "PF5(ADC5/TMS)_4") (pintype "bidirectional"))
    )
    (net (code "63") (name "unconnected-(U1-PF6(ADC6{slash}TDO)-Pad5)") (class "Default")
      (node (ref "U1") (pin "5") (pinfunction "PF6(ADC6/TDO)_5") (pintype "bidirectional"))
    )
    (net (code "64") (name "unconnected-(U1-PG4(TOSC1)-Pad18)") (class "Default")
      (node (ref "U1") (pin "18") (pinfunction "PG4(TOSC1)_18") (pintype "bidirectional"))
    )
    (net (code "65") (name "unconnected-(U1-PG5(OC0B)-Pad19)") (class "Default")
      (node (ref "U1") (pin "19") (pinfunction "PG5(OC0B)_19") (pintype "bidirectional"))
    )
    (net (code "66") (name "unconnected-(U1-RSTON-Pad13)") (class "Default")
      (node (ref "U1") (pin "13") (pinfunction "RSTON_13") (pintype "bidirectional"))
    )
    (net (code "67") (name "unconnected-(U2-PadINT1)") (class "Default")
      (node (ref "U2") (pin "INT1") (pinfunction "INT1_INT1") (pintype "bidirectional"))
    )
    (net (code "68") (name "unconnected-(U2-PadINT2)") (class "Default")
      (node (ref "U2") (pin "INT2") (pinfunction "INT2_INT2") (pintype "bidirectional"))
    )
    (net (code "69") (name "unconnected-(U2-PadOCS_AUX)") (class "Default")
      (node (ref "U2") (pin "OCS_AUX") (pinfunction "OCS_AUX_OCS_AUX") (pintype "bidirectional"))
    )
    (net (code "70") (name "unconnected-(U2-PadSDO_AUX)") (class "Default")
      (node (ref "U2") (pin "SDO_AUX") (pinfunction "SDO_AUX_SDO_AUX") (pintype "bidirectional"))
    )
  )
)
